# Phaser.net
KiCad netlist of a schematic drawn in Altium Designer
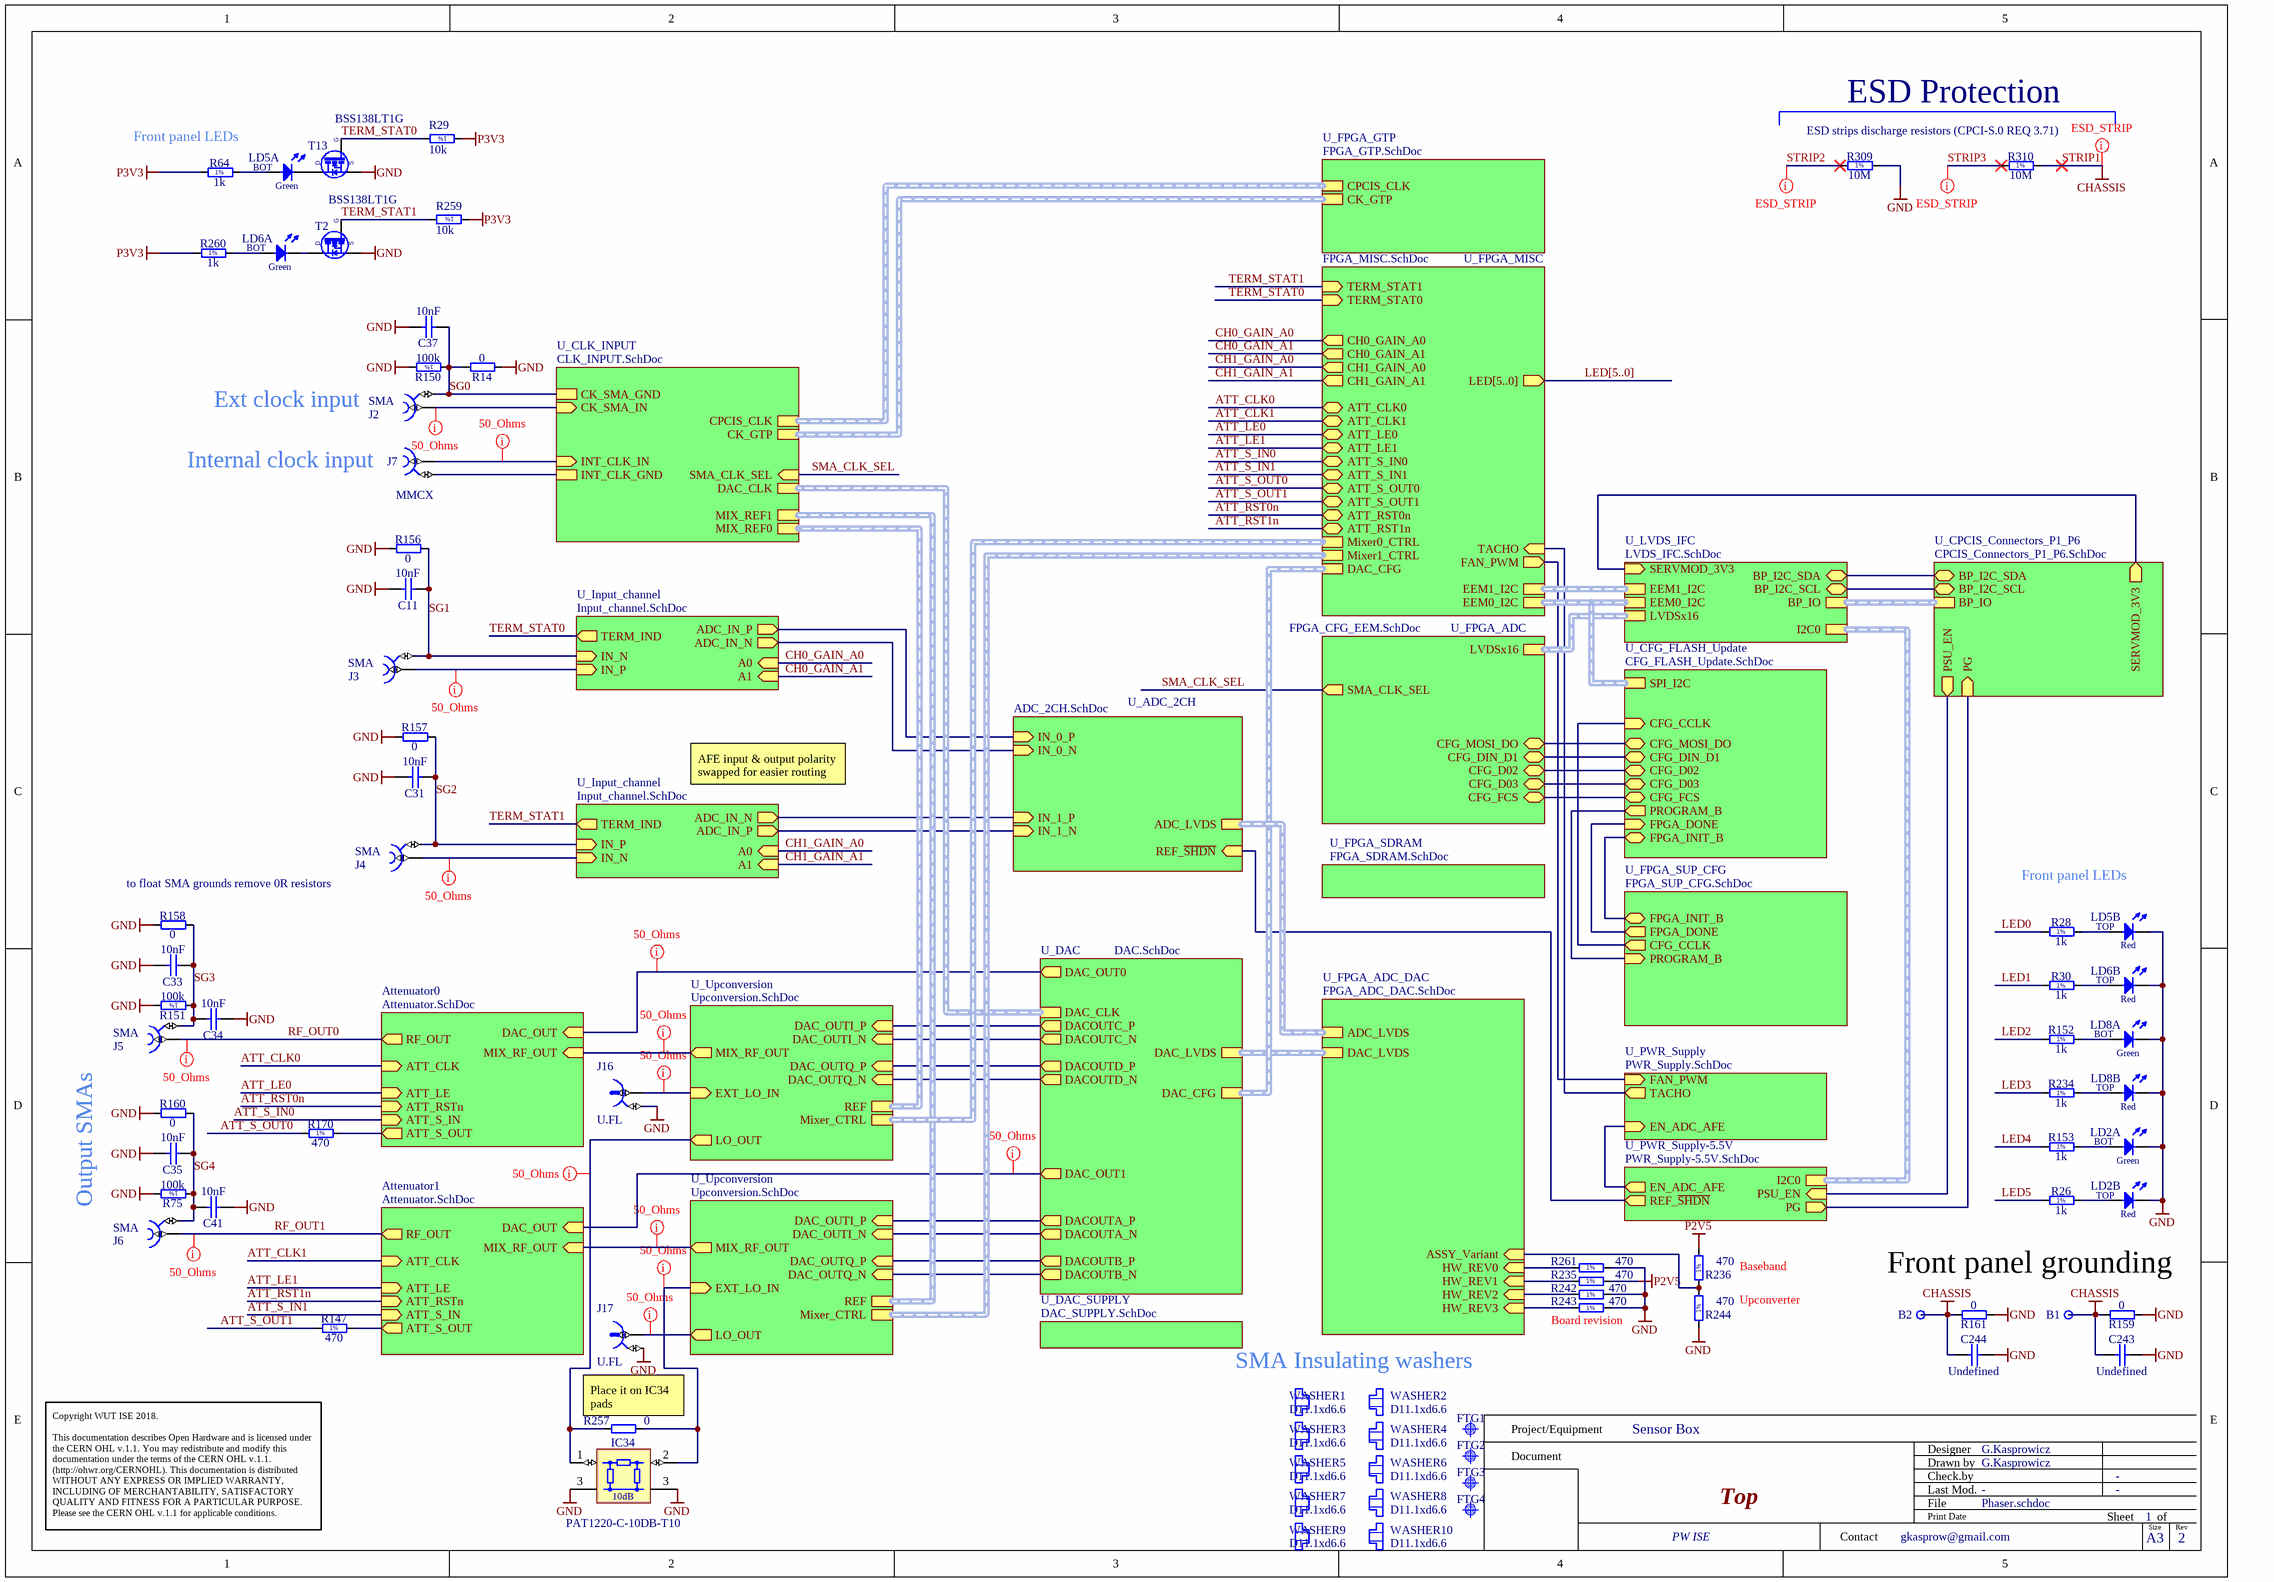
[diagram p0: Phaser.schdoc]

(export (version "E")
  (design (tool "Eeschema 10.0.6"))
  (components
    (comp (ref "B1")
      (value "Plated Hole")
      (footprint "MTG270_500")
      (description "Single Terminal Socket")
      (fields (field (name "PART NUMBER") "PLATED_HOLE2.7_PAD5.0") (field (name "AUTHOR") "CERN DEM JMW"))
      (libsource (lib "Eletro-mechanical") (part "Single Terminal Socket"))
    )
    (comp (ref "B2")
      (value "Plated Hole")
      (footprint "MTG270_500")
      (description "Single Terminal Socket")
      (fields (field (name "PART NUMBER") "PLATED_HOLE2.7_PAD5.0") (field (name "AUTHOR") "CERN DEM JMW"))
      (libsource (lib "Eletro-mechanical") (part "Single Terminal Socket"))
    )
    (comp (ref "C11")
      (value "10nF")
      (footprint "CAPC1005X55N")
      (description "Non-polarised capacitor")
      (fields
        (field (name "PART NUMBER") "CC0402_10NF_16V_10%_X7R")
        (field (name "VOLTAGE") "16V")
        (field (name "AUTHOR") "CERN DEM JLC")
      )
      (libsource (lib "Capacitors") (part "Capacitor - non polarized"))
    )
    (comp (ref "C31")
      (value "10nF")
      (footprint "CAPC1005X55N")
      (description "Non-polarised capacitor")
      (fields
        (field (name "PART NUMBER") "CC0402_10NF_16V_10%_X7R")
        (field (name "VOLTAGE") "16V")
        (field (name "AUTHOR") "CERN DEM JLC")
      )
      (libsource (lib "Capacitors") (part "Capacitor - non polarized"))
    )
    (comp (ref "C33")
      (value "10nF")
      (footprint "CAPC1005X55N")
      (description "Non-polarised capacitor")
      (fields
        (field (name "PART NUMBER") "CC0402_10NF_16V_10%_X7R")
        (field (name "VOLTAGE") "16V")
        (field (name "AUTHOR") "CERN DEM JLC")
      )
      (libsource (lib "Capacitors") (part "Capacitor - non polarized"))
    )
    (comp (ref "C34")
      (value "10nF")
      (footprint "CAPC1005X55N")
      (description "Non-polarised capacitor")
      (fields
        (field (name "PART NUMBER") "CC0402_10NF_16V_10%_X7R")
        (field (name "VOLTAGE") "16V")
        (field (name "AUTHOR") "CERN DEM JLC")
      )
      (libsource (lib "Capacitors") (part "Capacitor - non polarized"))
    )
    (comp (ref "C35")
      (value "10nF")
      (footprint "CAPC1005X55N")
      (description "Non-polarised capacitor")
      (fields
        (field (name "PART NUMBER") "CC0402_10NF_16V_10%_X7R")
        (field (name "VOLTAGE") "16V")
        (field (name "AUTHOR") "CERN DEM JLC")
      )
      (libsource (lib "Capacitors") (part "Capacitor - non polarized"))
    )
    (comp (ref "C37")
      (value "10nF")
      (footprint "CAPC1005X55N")
      (description "Non-polarised capacitor")
      (fields
        (field (name "PART NUMBER") "CC0402_10NF_16V_10%_X7R")
        (field (name "VOLTAGE") "16V")
        (field (name "AUTHOR") "CERN DEM JLC")
      )
      (libsource (lib "Capacitors") (part "Capacitor - non polarized"))
    )
    (comp (ref "C41")
      (value "10nF")
      (footprint "CAPC1005X55N")
      (description "Non-polarised capacitor")
      (fields
        (field (name "PART NUMBER") "CC0402_10NF_16V_10%_X7R")
        (field (name "VOLTAGE") "16V")
        (field (name "AUTHOR") "CERN DEM JLC")
      )
      (libsource (lib "Capacitors") (part "Capacitor - non polarized"))
    )
    (comp (ref "C243")
      (value "Undefined")
      (footprint "CAPC2012X135N")
      (description "Non-polarised capacitor")
      (fields (field (name "PART NUMBER") "CC0805_NO-VALUE") (field (name "AUTHOR") "CERN DEM JLC"))
      (libsource (lib "Capacitors") (part "Capacitor - non polarized"))
    )
    (comp (ref "C244")
      (value "Undefined")
      (footprint "CAPC2012X135N")
      (description "Non-polarised capacitor")
      (fields (field (name "PART NUMBER") "CC0805_NO-VALUE") (field (name "AUTHOR") "CERN DEM JLC"))
      (libsource (lib "Capacitors") (part "Capacitor - non polarized"))
    )
    (comp (ref "FTG1")
      (value "Use only in PCB")
      (footprint "FIDUCIAL_TOP_C100-200")
      (description "Fiducial Target")
      (fields (field (name "PART NUMBER") "FIDUCIAL_TARGET_C100-200") (field (name "AUTHOR") "CERN DEM JLC"))
      (libsource (lib "Eletro-mechanical") (part "Fiducial Target"))
    )
    (comp (ref "FTG2")
      (value "Use only in PCB")
      (footprint "FIDUCIAL_TOP_S100-200")
      (description "Fiducial Target")
      (fields (field (name "PART NUMBER") "FIDUCIAL_TARGET_S100-200") (field (name "AUTHOR") "CERN DEM JLC"))
      (libsource (lib "Eletro-mechanical") (part "Fiducial Target"))
    )
    (comp (ref "FTG3")
      (value "Use only in PCB")
      (footprint "FIDUCIAL_TOP_S100-200")
      (description "Fiducial Target")
      (fields (field (name "PART NUMBER") "FIDUCIAL_TARGET_S100-200") (field (name "AUTHOR") "CERN DEM JLC"))
      (libsource (lib "Eletro-mechanical") (part "Fiducial Target"))
    )
    (comp (ref "FTG4")
      (value "Use only in PCB")
      (footprint "FIDUCIAL_TOP_S100-200")
      (description "Fiducial Target")
      (fields (field (name "PART NUMBER") "FIDUCIAL_TARGET_S100-200") (field (name "AUTHOR") "CERN DEM JLC"))
      (libsource (lib "Eletro-mechanical") (part "Fiducial Target"))
    )
    (comp (ref "IC34")
      (value "PAT1220-C-10DB-T10")
      (footprint "SUSUMU_PAT1220")
      (description "DC to 10GHz, 100mW, 50 Ohm, 10dB, Precision Chip Attenuator")
      (fields (field (name "MANUFACTURER") "SUSUMU") (field (name "AUTHOR") "CERN DEM MR"))
      (libsource (lib "ICs And Semiconductors") (part "PAT1220-C-10DB"))
    )
    (comp (ref "J2")
      (value "SMA")
      (footprint "AMPHENOL_132203-14")
      (description "50 Ohm Through Hole SMA Right Angle PCB Jack")
      (fields
        (field (name "PART NUMBER") "AMPHENOL_132203-14")
        (field (name "MANUFACTURER") "AMPHENOL")
        (field (name "AUTHOR") "GK")
      )
      (libsource (lib "Connectors") (part "CON_SMA_AMP_132203-14"))
    )
    (comp (ref "J3")
      (value "SMA")
      (footprint "AMPHENOL_132203-14")
      (description "50 Ohm Through Hole SMA Right Angle PCB Jack")
      (fields
        (field (name "PART NUMBER") "AMPHENOL_132203-14")
        (field (name "MANUFACTURER") "AMPHENOL")
        (field (name "AUTHOR") "GK")
      )
      (libsource (lib "Connectors") (part "CON_SMA_AMP_132203-14"))
    )
    (comp (ref "J4")
      (value "SMA")
      (footprint "AMPHENOL_132203-14")
      (description "50 Ohm Through Hole SMA Right Angle PCB Jack")
      (fields
        (field (name "PART NUMBER") "AMPHENOL_132203-14")
        (field (name "MANUFACTURER") "AMPHENOL")
        (field (name "AUTHOR") "GK")
      )
      (libsource (lib "Connectors") (part "CON_SMA_AMP_132203-14"))
    )
    (comp (ref "J5")
      (value "SMA")
      (footprint "AMPHENOL_132203-14")
      (description "50 Ohm Through Hole SMA Right Angle PCB Jack")
      (fields
        (field (name "PART NUMBER") "AMPHENOL_132203-14")
        (field (name "MANUFACTURER") "AMPHENOL")
        (field (name "AUTHOR") "GK")
      )
      (libsource (lib "Connectors") (part "CON_SMA_AMP_132203-14"))
    )
    (comp (ref "J6")
      (value "SMA")
      (footprint "AMPHENOL_132203-14")
      (description "50 Ohm Through Hole SMA Right Angle PCB Jack")
      (fields
        (field (name "PART NUMBER") "AMPHENOL_132203-14")
        (field (name "MANUFACTURER") "AMPHENOL")
        (field (name "AUTHOR") "GK")
      )
      (libsource (lib "Connectors") (part "CON_SMA_AMP_132203-14"))
    )
    (comp (ref "J7")
      (value "MMCX")
      (footprint "SAMTEC_MMCX-J-P-H-ST-TH1")
      (fields
        (field (name "PART NUMBER") "SAMTEC_MMCX-J-P-H-ST-TH1")
        (field (name "MANUFACTURER") "SAMTEC")
        (field (name "MANUFACTURER PART NUMBER") "MMCX-J-P-H-ST-TH1")
        (field (name "AUTHOR") "CERN DEM JLC")
      )
      (libsource (lib "Connectors") (part "Coax_1Female_1Shield"))
    )
    (comp (ref "J16")
      (value "U.FL")
      (footprint "HIROSE_U.FL-R-SMT-1(10)")
      (fields
        (field (name "MANUFACTURER") "HIROSE (HRS)")
        (field (name "MANUFACTURER PART NUMBER") "U.FL-R-SMT-1(10)")
        (field (name "PART NUMBER") "HIROSE_U.FL-R-SMT-1(10)")
        (field (name "AUTHOR") "CERN DEM JLC")
      )
      (libsource (lib "Connectors") (part "Coax_1Male_1Shield"))
    )
    (comp (ref "J17")
      (value "U.FL")
      (footprint "HIROSE_U.FL-R-SMT-1(10)")
      (fields
        (field (name "MANUFACTURER") "HIROSE (HRS)")
        (field (name "MANUFACTURER PART NUMBER") "U.FL-R-SMT-1(10)")
        (field (name "PART NUMBER") "HIROSE_U.FL-R-SMT-1(10)")
        (field (name "AUTHOR") "CERN DEM JLC")
      )
      (libsource (lib "Connectors") (part "Coax_1Male_1Shield"))
    )
    (comp (ref "LD2")
      (value "Red/Green")
      (footprint "LED_DIALIGHT_571-0112F")
      (description "2x LED  Botom Green, Top Red")
      (fields
        (field (name "PART NUMBER") "LED_DIALIGHT_571-0112F")
        (field (name "MANUFACTURER") "DIALIGHT")
        (field (name "AUTHOR") "CERN DEM JLC")
      )
      (libsource (lib "ICs And Semiconductors") (part "LED x2 G-1C2A-BOT_R-3C4A-TOP"))
    )
    (comp (ref "LD5")
      (value "Red/Green")
      (footprint "LED_DIALIGHT_571-0112F")
      (description "2x LED  Botom Green, Top Red")
      (fields
        (field (name "PART NUMBER") "LED_DIALIGHT_571-0112F")
        (field (name "MANUFACTURER") "DIALIGHT")
        (field (name "AUTHOR") "CERN DEM JLC")
      )
      (libsource (lib "ICs And Semiconductors") (part "LED x2 G-1C2A-BOT_R-3C4A-TOP"))
    )
    (comp (ref "LD6")
      (value "Red/Green")
      (footprint "LED_DIALIGHT_571-0112F")
      (description "2x LED  Botom Green, Top Red")
      (fields
        (field (name "PART NUMBER") "LED_DIALIGHT_571-0112F")
        (field (name "MANUFACTURER") "DIALIGHT")
        (field (name "AUTHOR") "CERN DEM JLC")
      )
      (libsource (lib "ICs And Semiconductors") (part "LED x2 G-1C2A-BOT_R-3C4A-TOP"))
    )
    (comp (ref "LD8")
      (value "Red/Green")
      (footprint "LED_DIALIGHT_571-0112F")
      (description "2x LED  Botom Green, Top Red")
      (fields
        (field (name "PART NUMBER") "LED_DIALIGHT_571-0112F")
        (field (name "MANUFACTURER") "DIALIGHT")
        (field (name "AUTHOR") "CERN DEM JLC")
      )
      (libsource (lib "ICs And Semiconductors") (part "LED x2 G-1C2A-BOT_R-3C4A-TOP"))
    )
    (comp (ref "R14")
      (value "0")
      (footprint "RESC1608X55N")
      (description "Resistor")
      (fields
        (field (name "PART NUMBER") "R0603_0R_JUMPER")
        (field (name "MANUFACTURER") "GENERIC")
        (field (name "AUTHOR") "CERN DEM JLC")
      )
      (libsource (lib "Resistors") (part "Resistor"))
    )
    (comp (ref "R26")
      (value "1k")
      (footprint "RESC1005X40N")
      (description "Resistor - 1%")
      (fields
        (field (name "PART NUMBER") "R0402_1K_1%_0.0625W_100PPM")
        (field (name "POWER") "0.0625W")
        (field (name "AUTHOR") "CERN DEM JLC")
      )
      (libsource (lib "Resistors") (part "Resistor - 1%"))
    )
    (comp (ref "R28")
      (value "1k")
      (footprint "RESC1005X40N")
      (description "Resistor - 1%")
      (fields
        (field (name "PART NUMBER") "R0402_1K_1%_0.0625W_100PPM")
        (field (name "POWER") "0.0625W")
        (field (name "AUTHOR") "CERN DEM JLC")
      )
      (libsource (lib "Resistors") (part "Resistor - 1%"))
    )
    (comp (ref "R29")
      (value "10k")
      (footprint "RESC1005X40N")
      (description "Resistor - 1%")
      (fields
        (field (name "PART NUMBER") "R0402_10K_1%_0.0625W_100PPM")
        (field (name "POWER") "0.0625W")
        (field (name "AUTHOR") "CERN DEM JLC")
      )
      (libsource (lib "Resistors") (part "Resistor - 1%"))
    )
    (comp (ref "R30")
      (value "1k")
      (footprint "RESC1005X40N")
      (description "Resistor - 1%")
      (fields
        (field (name "PART NUMBER") "R0402_1K_1%_0.0625W_100PPM")
        (field (name "POWER") "0.0625W")
        (field (name "AUTHOR") "CERN DEM JLC")
      )
      (libsource (lib "Resistors") (part "Resistor - 1%"))
    )
    (comp (ref "R64")
      (value "1k")
      (footprint "RESC1005X40N")
      (description "Resistor - 1%")
      (fields
        (field (name "PART NUMBER") "R0402_1K_1%_0.0625W_100PPM")
        (field (name "POWER") "0.0625W")
        (field (name "AUTHOR") "CERN DEM JLC")
      )
      (libsource (lib "Resistors") (part "Resistor - 1%"))
    )
    (comp (ref "R75")
      (value "100k")
      (footprint "RESC1005X40N")
      (description "Resistor - 1%")
      (fields
        (field (name "PART NUMBER") "R0402_100K_1%_0.0625W_100PPM")
        (field (name "MANUFACTURER") "GENERIC")
        (field (name "AUTHOR") "CERN DEM JLC")
      )
      (libsource (lib "Resistors") (part "Resistor - 1%"))
    )
    (comp (ref "R147")
      (value "470")
      (footprint "RESC1005X40N")
      (description "Resistor - 1%")
      (fields
        (field (name "PART NUMBER") "R0402_470R_1%_0.0625W_100PPM")
        (field (name "POWER") "0.0625W")
        (field (name "AUTHOR") "CERN DEM JLC")
      )
      (libsource (lib "Resistors") (part "Resistor - 1%"))
    )
    (comp (ref "R150")
      (value "100k")
      (footprint "RESC1005X40N")
      (description "Resistor - 1%")
      (fields
        (field (name "PART NUMBER") "R0402_100K_1%_0.0625W_100PPM")
        (field (name "MANUFACTURER") "GENERIC")
        (field (name "AUTHOR") "CERN DEM JLC")
      )
      (libsource (lib "Resistors") (part "Resistor - 1%"))
    )
    (comp (ref "R151")
      (value "100k")
      (footprint "RESC1005X40N")
      (description "Resistor - 1%")
      (fields
        (field (name "PART NUMBER") "R0402_100K_1%_0.0625W_100PPM")
        (field (name "MANUFACTURER") "GENERIC")
        (field (name "AUTHOR") "CERN DEM JLC")
      )
      (libsource (lib "Resistors") (part "Resistor - 1%"))
    )
    (comp (ref "R152")
      (value "1k")
      (footprint "RESC1005X40N")
      (description "Resistor - 1%")
      (fields
        (field (name "PART NUMBER") "R0402_1K_1%_0.0625W_100PPM")
        (field (name "POWER") "0.0625W")
        (field (name "AUTHOR") "CERN DEM JLC")
      )
      (libsource (lib "Resistors") (part "Resistor - 1%"))
    )
    (comp (ref "R153")
      (value "1k")
      (footprint "RESC1005X40N")
      (description "Resistor - 1%")
      (fields
        (field (name "PART NUMBER") "R0402_1K_1%_0.0625W_100PPM")
        (field (name "POWER") "0.0625W")
        (field (name "AUTHOR") "CERN DEM JLC")
      )
      (libsource (lib "Resistors") (part "Resistor - 1%"))
    )
    (comp (ref "R156")
      (value "0")
      (footprint "RESC1608X55N")
      (description "Resistor")
      (fields
        (field (name "PART NUMBER") "R0603_0R_JUMPER")
        (field (name "MANUFACTURER") "GENERIC")
        (field (name "AUTHOR") "CERN DEM JLC")
      )
      (libsource (lib "Resistors") (part "Resistor"))
    )
    (comp (ref "R157")
      (value "0")
      (footprint "RESC1608X55N")
      (description "Resistor")
      (fields
        (field (name "PART NUMBER") "R0603_0R_JUMPER")
        (field (name "MANUFACTURER") "GENERIC")
        (field (name "AUTHOR") "CERN DEM JLC")
      )
      (libsource (lib "Resistors") (part "Resistor"))
    )
    (comp (ref "R158")
      (value "0")
      (footprint "RESC1608X55N")
      (description "Resistor")
      (fields
        (field (name "PART NUMBER") "R0603_0R_JUMPER")
        (field (name "MANUFACTURER") "GENERIC")
        (field (name "AUTHOR") "CERN DEM JLC")
      )
      (libsource (lib "Resistors") (part "Resistor"))
    )
    (comp (ref "R159")
      (value "0")
      (footprint "RESC1608X55N")
      (description "Resistor")
      (fields
        (field (name "PART NUMBER") "R0603_0R_JUMPER")
        (field (name "MANUFACTURER") "GENERIC")
        (field (name "AUTHOR") "CERN DEM JLC")
      )
      (libsource (lib "Resistors") (part "Resistor"))
    )
    (comp (ref "R160")
      (value "0")
      (footprint "RESC1608X55N")
      (description "Resistor")
      (fields
        (field (name "PART NUMBER") "R0603_0R_JUMPER")
        (field (name "MANUFACTURER") "GENERIC")
        (field (name "AUTHOR") "CERN DEM JLC")
      )
      (libsource (lib "Resistors") (part "Resistor"))
    )
    (comp (ref "R161")
      (value "0")
      (footprint "RESC1608X55N")
      (description "Resistor")
      (fields
        (field (name "PART NUMBER") "R0603_0R_JUMPER")
        (field (name "MANUFACTURER") "GENERIC")
        (field (name "AUTHOR") "CERN DEM JLC")
      )
      (libsource (lib "Resistors") (part "Resistor"))
    )
    (comp (ref "R170")
      (value "470")
      (footprint "RESC1005X40N")
      (description "Resistor - 1%")
      (fields
        (field (name "PART NUMBER") "R0402_470R_1%_0.0625W_100PPM")
        (field (name "POWER") "0.0625W")
        (field (name "AUTHOR") "CERN DEM JLC")
      )
      (libsource (lib "Resistors") (part "Resistor - 1%"))
    )
    (comp (ref "R234")
      (value "1k")
      (footprint "RESC1005X40N")
      (description "Resistor - 1%")
      (fields
        (field (name "PART NUMBER") "R0402_1K_1%_0.0625W_100PPM")
        (field (name "POWER") "0.0625W")
        (field (name "AUTHOR") "CERN DEM JLC")
      )
      (libsource (lib "Resistors") (part "Resistor - 1%"))
    )
    (comp (ref "R235")
      (value "470")
      (footprint "RESC1005X40N")
      (description "Resistor - 1%")
      (fields
        (field (name "PART NUMBER") "R0402_470R_1%_0.0625W_100PPM")
        (field (name "POWER") "0.0625W")
        (field (name "AUTHOR") "CERN DEM JLC")
      )
      (libsource (lib "Resistors") (part "Resistor - 1%"))
    )
    (comp (ref "R236")
      (value "470")
      (footprint "RESC1005X40N")
      (description "Resistor - 1%")
      (fields
        (field (name "PART NUMBER") "R0402_470R_1%_0.0625W_100PPM")
        (field (name "POWER") "0.0625W")
        (field (name "AUTHOR") "CERN DEM JLC")
      )
      (libsource (lib "Resistors") (part "Resistor - 1%"))
    )
    (comp (ref "R242")
      (value "470")
      (footprint "RESC1005X40N")
      (description "Resistor - 1%")
      (fields
        (field (name "PART NUMBER") "R0402_470R_1%_0.0625W_100PPM")
        (field (name "POWER") "0.0625W")
        (field (name "AUTHOR") "CERN DEM JLC")
      )
      (libsource (lib "Resistors") (part "Resistor - 1%"))
    )
    (comp (ref "R243")
      (value "470")
      (footprint "RESC1005X40N")
      (description "Resistor - 1%")
      (fields
        (field (name "PART NUMBER") "R0402_470R_1%_0.0625W_100PPM")
        (field (name "POWER") "0.0625W")
        (field (name "AUTHOR") "CERN DEM JLC")
      )
      (libsource (lib "Resistors") (part "Resistor - 1%"))
    )
    (comp (ref "R244")
      (value "470")
      (footprint "RESC1005X40N")
      (description "Resistor - 1%")
      (fields
        (field (name "PART NUMBER") "R0402_470R_1%_0.0625W_100PPM")
        (field (name "POWER") "0.0625W")
        (field (name "AUTHOR") "CERN DEM JLC")
      )
      (libsource (lib "Resistors") (part "Resistor - 1%"))
    )
    (comp (ref "R257")
      (value "0")
      (footprint "RESC1005X40N")
      (description "Resistor")
      (fields
        (field (name "PART NUMBER") "R0402_0R_JUMPER")
        (field (name "MANUFACTURER") "GENERIC")
        (field (name "AUTHOR") "CERN DEM JLC")
      )
      (libsource (lib "Resistors") (part "Resistor"))
    )
    (comp (ref "R259")
      (value "10k")
      (footprint "RESC1005X40N")
      (description "Resistor - 1%")
      (fields
        (field (name "PART NUMBER") "R0402_10K_1%_0.0625W_100PPM")
        (field (name "POWER") "0.0625W")
        (field (name "AUTHOR") "CERN DEM JLC")
      )
      (libsource (lib "Resistors") (part "Resistor - 1%"))
    )
    (comp (ref "R260")
      (value "1k")
      (footprint "RESC1005X40N")
      (description "Resistor - 1%")
      (fields
        (field (name "PART NUMBER") "R0402_1K_1%_0.0625W_100PPM")
        (field (name "POWER") "0.0625W")
        (field (name "AUTHOR") "CERN DEM JLC")
      )
      (libsource (lib "Resistors") (part "Resistor - 1%"))
    )
    (comp (ref "R261")
      (value "470")
      (footprint "RESC1005X40N")
      (description "Resistor - 1%")
      (fields
        (field (name "PART NUMBER") "R0402_470R_1%_0.0625W_100PPM")
        (field (name "POWER") "0.0625W")
        (field (name "AUTHOR") "CERN DEM JLC")
      )
      (libsource (lib "Resistors") (part "Resistor - 1%"))
    )
    (comp (ref "R309")
      (value "10M")
      (footprint "RESC2113X55N")
      (description "Resistor - 1%")
      (fields
        (field (name "PART NUMBER") "R0805_10M_1%_0.125W_100PPM_VISHAY_CRCW e3")
        (field (name "POWER") "0.125W")
        (field (name "AUTHOR") "CERN DEM BC")
      )
      (libsource (lib "Resistors") (part "Resistor - 1%"))
    )
    (comp (ref "R310")
      (value "10M")
      (footprint "RESC2113X55N")
      (description "Resistor - 1%")
      (fields
        (field (name "PART NUMBER") "R0805_10M_1%_0.125W_100PPM_VISHAY_CRCW e3")
        (field (name "POWER") "0.125W")
        (field (name "AUTHOR") "CERN DEM BC")
      )
      (libsource (lib "Resistors") (part "Resistor - 1%"))
    )
    (comp (ref "T2")
      (value "BSS138LT1G")
      (footprint "SOT95P240X110-3N")
      (description "N-CHANNEL MOSFET WITH DIODE")
      (fields (field (name "MANUFACTURER") "ON SEMICONDUCTOR") (field (name "AUTHOR") "CERN DEM JLC"))
      (libsource (lib "ICs And Semiconductors") (part "N-MOSFET-D 1G 2S 3D"))
    )
    (comp (ref "T13")
      (value "BSS138LT1G")
      (footprint "SOT95P240X110-3N")
      (description "N-CHANNEL MOSFET WITH DIODE")
      (fields (field (name "MANUFACTURER") "ON SEMICONDUCTOR") (field (name "AUTHOR") "CERN DEM JLC"))
      (libsource (lib "ICs And Semiconductors") (part "N-MOSFET-D 1G 2S 3D"))
    )
    (comp (ref "WASHER1")
      (value "D11.1xd6.6")
      (footprint "Keystone_7687")
      (description "SMA_Shoulder Washer")
      (fields (field (name "PART NUMBER") "custom 3D") (field (name "AUTHOR") "GK"))
      (libsource (lib "LIBRARY_SCH") (part "Keystone_7687"))
    )
    (comp (ref "WASHER2")
      (value "D11.1xd6.6")
      (footprint "Keystone_7687")
      (description "SMA_Shoulder Washer")
      (fields (field (name "PART NUMBER") "custom 3D") (field (name "AUTHOR") "GK"))
      (libsource (lib "LIBRARY_SCH") (part "Keystone_7687"))
    )
    (comp (ref "WASHER3")
      (value "D11.1xd6.6")
      (footprint "Keystone_7687")
      (description "SMA_Shoulder Washer")
      (fields (field (name "PART NUMBER") "custom 3D") (field (name "AUTHOR") "GK"))
      (libsource (lib "LIBRARY_SCH") (part "Keystone_7687"))
    )
    (comp (ref "WASHER4")
      (value "D11.1xd6.6")
      (footprint "Keystone_7687")
      (description "SMA_Shoulder Washer")
      (fields (field (name "PART NUMBER") "custom 3D") (field (name "AUTHOR") "GK"))
      (libsource (lib "LIBRARY_SCH") (part "Keystone_7687"))
    )
    (comp (ref "WASHER5")
      (value "D11.1xd6.6")
      (footprint "Keystone_7687")
      (description "SMA_Shoulder Washer")
      (fields (field (name "PART NUMBER") "custom 3D") (field (name "AUTHOR") "GK"))
      (libsource (lib "LIBRARY_SCH") (part "Keystone_7687"))
    )
    (comp (ref "WASHER6")
      (value "D11.1xd6.6")
      (footprint "Keystone_7687")
      (description "SMA_Shoulder Washer")
      (fields (field (name "PART NUMBER") "custom 3D") (field (name "AUTHOR") "GK"))
      (libsource (lib "LIBRARY_SCH") (part "Keystone_7687"))
    )
    (comp (ref "WASHER7")
      (value "D11.1xd6.6")
      (footprint "Keystone_7687")
      (description "SMA_Shoulder Washer")
      (fields (field (name "PART NUMBER") "custom 3D") (field (name "AUTHOR") "GK"))
      (libsource (lib "LIBRARY_SCH") (part "Keystone_7687"))
    )
    (comp (ref "WASHER8")
      (value "D11.1xd6.6")
      (footprint "Keystone_7687")
      (description "SMA_Shoulder Washer")
      (fields (field (name "PART NUMBER") "custom 3D") (field (name "AUTHOR") "GK"))
      (libsource (lib "LIBRARY_SCH") (part "Keystone_7687"))
    )
    (comp (ref "WASHER9")
      (value "D11.1xd6.6")
      (footprint "Keystone_7687")
      (description "SMA_Shoulder Washer")
      (fields (field (name "PART NUMBER") "custom 3D") (field (name "AUTHOR") "GK"))
      (libsource (lib "LIBRARY_SCH") (part "Keystone_7687"))
    )
    (comp (ref "WASHER10")
      (value "D11.1xd6.6")
      (footprint "Keystone_7687")
      (description "SMA_Shoulder Washer")
      (fields (field (name "PART NUMBER") "custom 3D") (field (name "AUTHOR") "GK"))
      (libsource (lib "LIBRARY_SCH") (part "Keystone_7687"))
    )
  )
  (nets
    (net (code "6") (name "/ASSY_Variant") (class "Default")
      (node (ref "R236") (pin "1") (pinfunction "1_1") (pintype "passive"))
      (node (ref "R244") (pin "2") (pinfunction "2_2") (pintype "passive"))
    )
    (net (code "15") (name "/ATT_S_OUT") (class "Default")
      (node (ref "R147") (pin "2") (pinfunction "2_2") (pintype "passive"))
    )
    (net (code "16") (name "/ATT_S_OUT0") (class "Default")
      (node (ref "R170") (pin "1") (pinfunction "1_1") (pintype "passive"))
    )
    (net (code "17") (name "/ATT_S_OUT1") (class "Default")
      (node (ref "R147") (pin "1") (pinfunction "1_1") (pintype "passive"))
    )
    (net (code "18") (name "/ATT_S_OUT_1") (class "Default")
      (node (ref "R170") (pin "2") (pinfunction "2_2") (pintype "passive"))
    )
    (net (code "33") (name "/CK_SMA_IN") (class "Default")
      (node (ref "J2") (pin "1") (pinfunction "1_1") (pintype "bidirectional"))
    )
    (net (code "51") (name "/EXT_LO_IN") (class "Default")
      (node (ref "IC34") (pin "2") (pinfunction "OUT_2") (pintype "bidirectional"))
      (node (ref "R257") (pin "1") (pinfunction "1_1") (pintype "passive"))
    )
    (net (code "52") (name "/EXT_LO_IN_1") (class "Default")
      (node (ref "J16") (pin "1") (pinfunction "1_1") (pintype "bidirectional"))
    )
    (net (code "56") (name "/HW_REV0") (class "Default")
      (node (ref "R261") (pin "1") (pinfunction "1_1") (pintype "passive"))
    )
    (net (code "57") (name "/HW_REV1") (class "Default")
      (node (ref "R235") (pin "1") (pinfunction "1_1") (pintype "passive"))
    )
    (net (code "58") (name "/HW_REV2") (class "Default")
      (node (ref "R242") (pin "1") (pinfunction "1_1") (pintype "passive"))
    )
    (net (code "59") (name "/HW_REV3") (class "Default")
      (node (ref "R243") (pin "1") (pinfunction "1_1") (pintype "passive"))
    )
    (net (code "61") (name "/INT_CLK_GND") (class "Default")
      (node (ref "J7") (pin "2") (pinfunction "2_2") (pintype "bidirectional"))
    )
    (net (code "62") (name "/INT_CLK_IN") (class "Default")
      (node (ref "J7") (pin "1") (pinfunction "1_1") (pintype "bidirectional"))
    )
    (net (code "63") (name "/IN_N") (class "Default")
      (node (ref "J4") (pin "1") (pinfunction "1_1") (pintype "bidirectional"))
    )
    (net (code "64") (name "/IN_P") (class "Default")
      (node (ref "J3") (pin "1") (pinfunction "1_1") (pintype "bidirectional"))
    )
    (net (code "65") (name "/LED0") (class "Default")
      (node (ref "R28") (pin "1") (pinfunction "1_1") (pintype "passive"))
    )
    (net (code "66") (name "/LED1") (class "Default")
      (node (ref "R30") (pin "1") (pinfunction "1_1") (pintype "passive"))
    )
    (net (code "67") (name "/LED2") (class "Default")
      (node (ref "R152") (pin "1") (pinfunction "1_1") (pintype "passive"))
    )
    (net (code "68") (name "/LED3") (class "Default")
      (node (ref "R234") (pin "1") (pinfunction "1_1") (pintype "passive"))
    )
    (net (code "69") (name "/LED4") (class "Default")
      (node (ref "R153") (pin "1") (pinfunction "1_1") (pintype "passive"))
    )
    (net (code "70") (name "/LED5") (class "Default")
      (node (ref "R26") (pin "1") (pinfunction "1_1") (pintype "passive"))
    )
    (net (code "72") (name "/LO_OUT") (class "Default")
      (node (ref "J17") (pin "1") (pinfunction "1_1") (pintype "bidirectional"))
    )
    (net (code "73") (name "/LO_OUT_1") (class "Default")
      (node (ref "IC34") (pin "1") (pinfunction "IN_1") (pintype "bidirectional"))
      (node (ref "R257") (pin "2") (pinfunction "2_2") (pintype "passive"))
    )
    (net (code "85") (name "/RF_OUT0") (class "Default")
      (node (ref "J5") (pin "1") (pinfunction "1_1") (pintype "bidirectional"))
    )
    (net (code "86") (name "/RF_OUT1") (class "Default")
      (node (ref "J6") (pin "1") (pinfunction "1_1") (pintype "bidirectional"))
    )
    (net (code "88") (name "/SG0") (class "Default")
      (node (ref "C37") (pin "1") (pinfunction "1_1") (pintype "passive"))
      (node (ref "J2") (pin "2") (pinfunction "2_2") (pintype "bidirectional"))
      (node (ref "R14") (pin "2") (pinfunction "2_2") (pintype "passive"))
      (node (ref "R150") (pin "2") (pinfunction "2_2") (pintype "passive"))
    )
    (net (code "89") (name "/SG1") (class "Default")
      (node (ref "C11") (pin "1") (pinfunction "1_1") (pintype "passive"))
      (node (ref "J3") (pin "2") (pinfunction "2_2") (pintype "bidirectional"))
      (node (ref "R156") (pin "2") (pinfunction "2_2") (pintype "passive"))
    )
    (net (code "90") (name "/SG2") (class "Default")
      (node (ref "C31") (pin "1") (pinfunction "1_1") (pintype "passive"))
      (node (ref "J4") (pin "2") (pinfunction "2_2") (pintype "bidirectional"))
      (node (ref "R157") (pin "2") (pinfunction "2_2") (pintype "passive"))
    )
    (net (code "91") (name "/SG3") (class "Default")
      (node (ref "C33") (pin "1") (pinfunction "1_1") (pintype "passive"))
      (node (ref "C34") (pin "2") (pinfunction "2_2") (pintype "passive"))
      (node (ref "J5") (pin "2") (pinfunction "2_2") (pintype "bidirectional"))
      (node (ref "R151") (pin "2") (pinfunction "2_2") (pintype "passive"))
      (node (ref "R158") (pin "2") (pinfunction "2_2") (pintype "passive"))
    )
    (net (code "92") (name "/SG4") (class "Default")
      (node (ref "C35") (pin "1") (pinfunction "1_1") (pintype "passive"))
      (node (ref "C41") (pin "2") (pinfunction "2_2") (pintype "passive"))
      (node (ref "J6") (pin "2") (pinfunction "2_2") (pintype "bidirectional"))
      (node (ref "R160") (pin "2") (pinfunction "2_2") (pintype "passive"))
      (node (ref "R75") (pin "2") (pinfunction "2_2") (pintype "passive"))
    )
    (net (code "95") (name "/STRIP2") (class "Default")
      (node (ref "R309") (pin "1") (pinfunction "1_1") (pintype "passive+no_connect"))
    )
    (net (code "96") (name "/STRIP3") (class "Default")
      (node (ref "R310") (pin "1") (pinfunction "1_1") (pintype "passive+no_connect"))
    )
    (net (code "98") (name "/TERM_STAT0") (class "Default")
      (node (ref "R29") (pin "2") (pinfunction "2_2") (pintype "passive"))
      (node (ref "T13") (pin "1") (pinfunction "G_1") (pintype "passive"))
    )
    (net (code "99") (name "/TERM_STAT1") (class "Default")
      (node (ref "R259") (pin "2") (pinfunction "2_2") (pintype "passive"))
      (node (ref "T2") (pin "1") (pinfunction "G_1") (pintype "passive"))
    )
    (net (code "100") (name "CHASSIS") (class "Default")
      (node (ref "B1") (pin "1") (pinfunction "1_1") (pintype "bidirectional"))
      (node (ref "B2") (pin "1") (pinfunction "1_1") (pintype "bidirectional"))
      (node (ref "C243") (pin "1") (pinfunction "1_1") (pintype "passive"))
      (node (ref "C244") (pin "1") (pinfunction "1_1") (pintype "passive"))
      (node (ref "R159") (pin "2") (pinfunction "2_2") (pintype "passive"))
      (node (ref "R161") (pin "2") (pinfunction "2_2") (pintype "passive"))
      (node (ref "R310") (pin "2") (pinfunction "2_2") (pintype "passive"))
    )
    (net (code "101") (name "GND") (class "Default")
      (node (ref "C11") (pin "2") (pinfunction "2_2") (pintype "passive"))
      (node (ref "C243") (pin "2") (pinfunction "2_2") (pintype "passive"))
      (node (ref "C244") (pin "2") (pinfunction "2_2") (pintype "passive"))
      (node (ref "C31") (pin "2") (pinfunction "2_2") (pintype "passive"))
      (node (ref "C33") (pin "2") (pinfunction "2_2") (pintype "passive"))
      (node (ref "C34") (pin "1") (pinfunction "1_1") (pintype "passive"))
      (node (ref "C35") (pin "2") (pinfunction "2_2") (pintype "passive"))
      (node (ref "C37") (pin "2") (pinfunction "2_2") (pintype "passive"))
      (node (ref "C41") (pin "1") (pinfunction "1_1") (pintype "passive"))
      (node (ref "IC34") (pin "3") (pinfunction "GND_3") (pintype "passive"))
      (node (ref "J16") (pin "2") (pinfunction "2_2") (pintype "bidirectional"))
      (node (ref "J17") (pin "2") (pinfunction "2_2") (pintype "bidirectional"))
      (node (ref "LD2") (pin "1") (pinfunction "C_1") (pintype "passive"))
      (node (ref "LD2") (pin "3") (pinfunction "C_3") (pintype "passive"))
      (node (ref "LD5") (pin "3") (pinfunction "C_3") (pintype "passive"))
      (node (ref "LD6") (pin "3") (pinfunction "C_3") (pintype "passive"))
      (node (ref "LD8") (pin "1") (pinfunction "C_1") (pintype "passive"))
      (node (ref "LD8") (pin "3") (pinfunction "C_3") (pintype "passive"))
      (node (ref "R14") (pin "1") (pinfunction "1_1") (pintype "passive"))
      (node (ref "R150") (pin "1") (pinfunction "1_1") (pintype "passive"))
      (node (ref "R151") (pin "1") (pinfunction "1_1") (pintype "passive"))
      (node (ref "R156") (pin "1") (pinfunction "1_1") (pintype "passive"))
      (node (ref "R157") (pin "1") (pinfunction "1_1") (pintype "passive"))
      (node (ref "R158") (pin "1") (pinfunction "1_1") (pintype "passive"))
      (node (ref "R159") (pin "1") (pinfunction "1_1") (pintype "passive"))
      (node (ref "R160") (pin "1") (pinfunction "1_1") (pintype "passive"))
      (node (ref "R161") (pin "1") (pinfunction "1_1") (pintype "passive"))
      (node (ref "R242") (pin "2") (pinfunction "2_2") (pintype "passive"))
      (node (ref "R243") (pin "2") (pinfunction "2_2") (pintype "passive"))
      (node (ref "R244") (pin "1") (pinfunction "1_1") (pintype "passive"))
      (node (ref "R261") (pin "2") (pinfunction "2_2") (pintype "passive"))
      (node (ref "R309") (pin "2") (pinfunction "2_2") (pintype "passive"))
      (node (ref "R75") (pin "1") (pinfunction "1_1") (pintype "passive"))
      (node (ref "T13") (pin "2") (pinfunction "S_2") (pintype "passive"))
      (node (ref "T2") (pin "2") (pinfunction "S_2") (pintype "passive"))
    )
    (net (code "102") (name "Net-(LD2A-A)") (class "Default")
      (node (ref "LD2") (pin "2") (pinfunction "A_2") (pintype "passive"))
      (node (ref "R153") (pin "2") (pinfunction "2_2") (pintype "passive"))
    )
    (net (code "103") (name "Net-(LD2B-A)") (class "Default")
      (node (ref "LD2") (pin "4") (pinfunction "A_4") (pintype "passive"))
      (node (ref "R26") (pin "2") (pinfunction "2_2") (pintype "passive"))
    )
    (net (code "104") (name "Net-(LD5A-A)") (class "Default")
      (node (ref "LD5") (pin "2") (pinfunction "A_2") (pintype "passive"))
      (node (ref "R64") (pin "2") (pinfunction "2_2") (pintype "passive"))
    )
    (net (code "105") (name "Net-(LD5A-C)") (class "Default")
      (node (ref "LD5") (pin "1") (pinfunction "C_1") (pintype "passive"))
      (node (ref "T13") (pin "3") (pinfunction "D_3") (pintype "passive"))
    )
    (net (code "106") (name "Net-(LD5B-A)") (class "Default")
      (node (ref "LD5") (pin "4") (pinfunction "A_4") (pintype "passive"))
      (node (ref "R28") (pin "2") (pinfunction "2_2") (pintype "passive"))
    )
    (net (code "107") (name "Net-(LD6A-A)") (class "Default")
      (node (ref "LD6") (pin "2") (pinfunction "A_2") (pintype "passive"))
      (node (ref "R260") (pin "2") (pinfunction "2_2") (pintype "passive"))
    )
    (net (code "108") (name "Net-(LD6A-C)") (class "Default")
      (node (ref "LD6") (pin "1") (pinfunction "C_1") (pintype "passive"))
      (node (ref "T2") (pin "3") (pinfunction "D_3") (pintype "passive"))
    )
    (net (code "109") (name "Net-(LD6B-A)") (class "Default")
      (node (ref "LD6") (pin "4") (pinfunction "A_4") (pintype "passive"))
      (node (ref "R30") (pin "2") (pinfunction "2_2") (pintype "passive"))
    )
    (net (code "110") (name "Net-(LD8A-A)") (class "Default")
      (node (ref "LD8") (pin "2") (pinfunction "A_2") (pintype "passive"))
      (node (ref "R152") (pin "2") (pinfunction "2_2") (pintype "passive"))
    )
    (net (code "111") (name "Net-(LD8B-A)") (class "Default")
      (node (ref "LD8") (pin "4") (pinfunction "A_4") (pintype "passive"))
      (node (ref "R234") (pin "2") (pinfunction "2_2") (pintype "passive"))
    )
    (net (code "112") (name "P2V5") (class "Default")
      (node (ref "R235") (pin "2") (pinfunction "2_2") (pintype "passive"))
      (node (ref "R236") (pin "2") (pinfunction "2_2") (pintype "passive"))
    )
    (net (code "113") (name "P3V3") (class "Default")
      (node (ref "R259") (pin "1") (pinfunction "1_1") (pintype "passive"))
      (node (ref "R260") (pin "1") (pinfunction "1_1") (pintype "passive"))
      (node (ref "R29") (pin "1") (pinfunction "1_1") (pintype "passive"))
      (node (ref "R64") (pin "1") (pinfunction "1_1") (pintype "passive"))
    )
  )
)
